# Power.net
KiCad netlist of a schematic drawn in Altium Designer
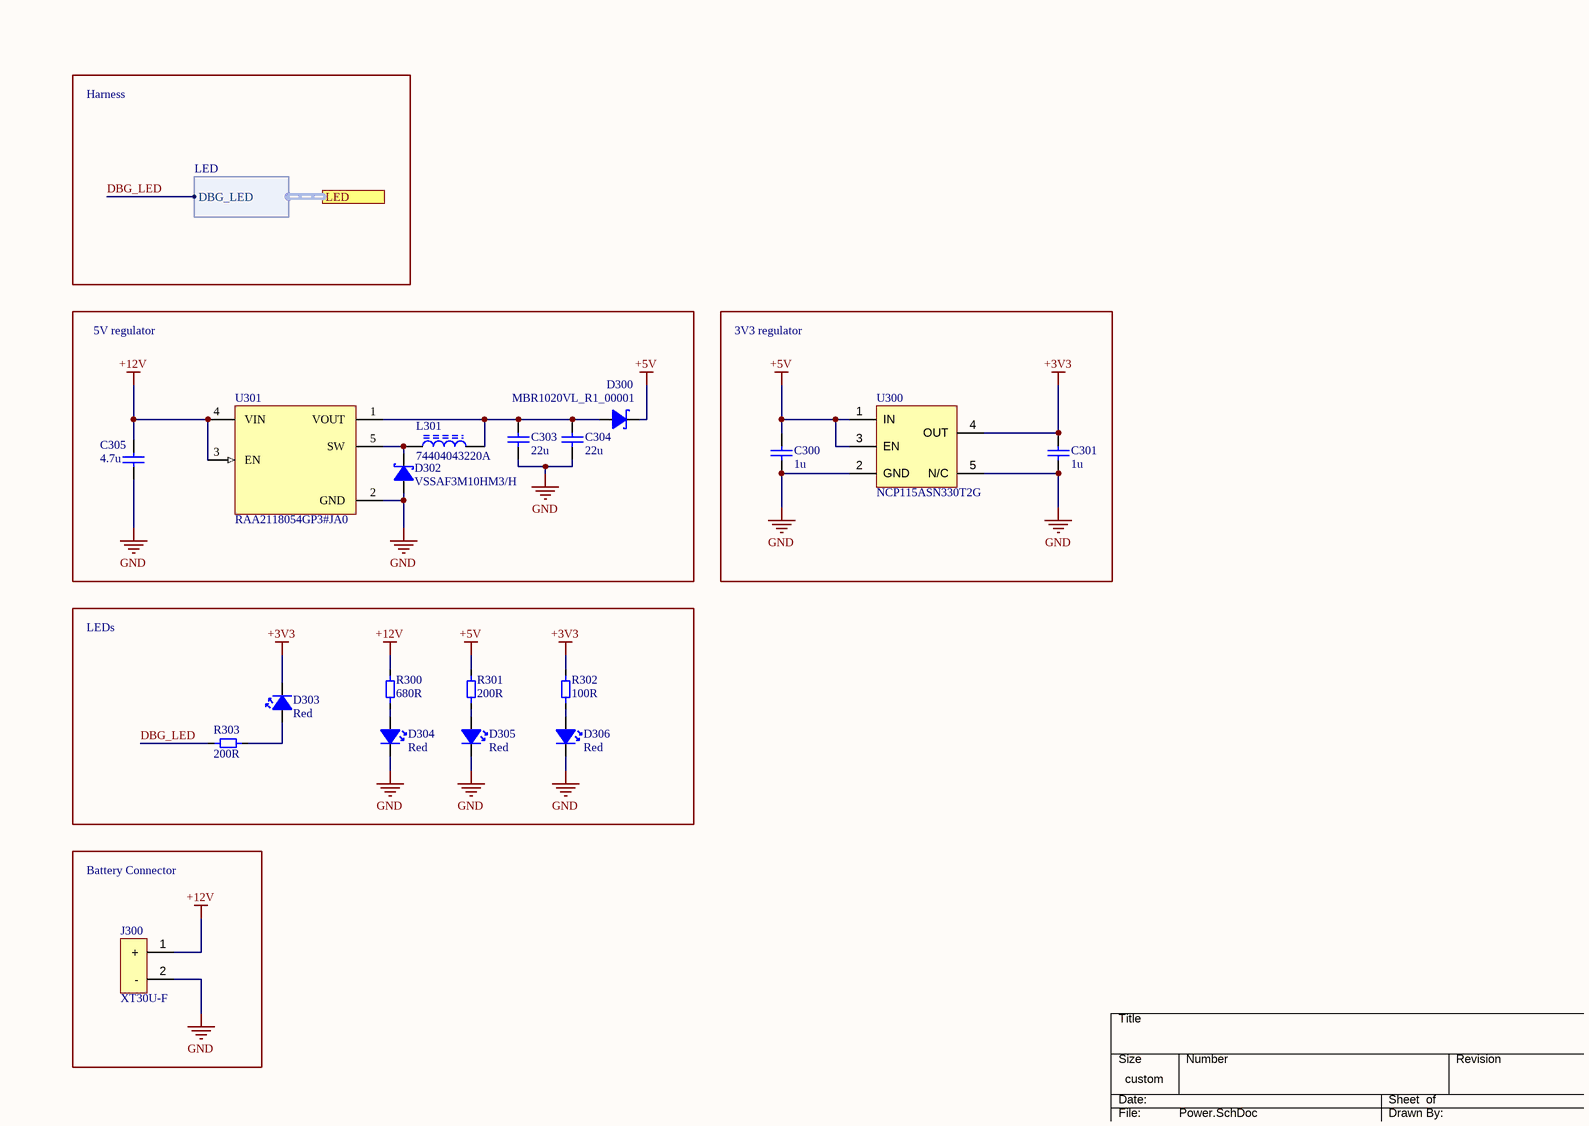
[diagram p0: Power.SchDoc]

(export (version "E")
  (design (tool "Eeschema 10.0.6"))
  (components
    (comp (ref "C300")
      (value "1u")
      (footprint "MLCC_0603_M")
      (description "MLCC, 0603, 1u, 10%, 50V, X5R")
      (fields (field (name "MANUFACTURER") "Any") (field (name "VOLTAGE") "50V"))
      (libsource (lib "Krakul Vault") (part "CAPACITOR_NONPOL_IEC"))
    )
    (comp (ref "C301")
      (value "1u")
      (footprint "MLCC_0603_M")
      (description "MLCC, 0603, 1u, 10%, 50V, X5R")
      (fields (field (name "MANUFACTURER") "Any") (field (name "VOLTAGE") "50V"))
      (libsource (lib "Krakul Vault") (part "CAPACITOR_NONPOL_IEC"))
    )
    (comp (ref "C303")
      (value "22u")
      (footprint "MLCC_0603_M")
      (description "MLCC, 0603, 22u, 10%, 16V, X5R")
      (fields (field (name "TOLERANCE") "10%") (field (name "MANUFACTURER") "Any"))
      (libsource (lib "Krakul Vault") (part "CAPACITOR_NONPOL_IEC"))
    )
    (comp (ref "C304")
      (value "22u")
      (footprint "MLCC_0603_M")
      (description "MLCC, 0603, 22u, 10%, 16V, X5R")
      (fields (field (name "TOLERANCE") "10%") (field (name "MANUFACTURER") "Any"))
      (libsource (lib "Krakul Vault") (part "CAPACITOR_NONPOL_IEC"))
    )
    (comp (ref "C305")
      (value "4.7u")
      (footprint "MLCC_1206_M")
      (description "MLCC, 1206, 4.7u, 10%, 35V, X5R")
      (fields (field (name "VOLTAGE") "35V") (field (name "TOLERANCE") "10%"))
      (libsource (lib "Krakul Vault") (part "CAPACITOR_NONPOL_IEC"))
    )
    (comp (ref "D300")
      (value "MBR1020VL_R1_00001")
      (footprint "FP-MBR1020VL_R1_00001-MFG")
      (description "Rectifier Diode, Schottky, 1 Phase, 1 Element, 1A, 20V V(RRM), Silicon")
      (fields (field (name "MANUFACTURER") "Panjit"))
      (libsource (lib "Krakul Vault") (part "Schottky generic 2 pins"))
    )
    (comp (ref "D302")
      (value "VSSAF3M10HM3/H")
      (footprint "VSSAF3M10HM3_H-Footprint-1")
      (description "Rectifier Diode, Schottky, 1 Phase, 1 Element, 2.3A, 100V V(RRM), Silicon, DO-221AC")
      (libsource (lib "Krakul Vault") (part "Schottky generic 2 pins"))
    )
    (comp (ref "D303")
      (value "Red")
      (footprint "0603 RED LED")
      (description "Generic red 0603 LED")
      (fields (field (name "PART NUMBER") "Any Red 0603 LED") (field (name "MANUFACTURER") "Any"))
      (libsource (lib "Krakul Vault") (part "LED generic"))
    )
    (comp (ref "D304")
      (value "Red")
      (footprint "0603 RED LED")
      (description "Generic red 0603 LED")
      (fields (field (name "PART NUMBER") "Any Red 0603 LED") (field (name "MANUFACTURER") "Any"))
      (libsource (lib "Krakul Vault") (part "LED generic"))
    )
    (comp (ref "D305")
      (value "Red")
      (footprint "0603 RED LED")
      (description "Generic red 0603 LED")
      (fields (field (name "PART NUMBER") "Any Red 0603 LED") (field (name "MANUFACTURER") "Any"))
      (libsource (lib "Krakul Vault") (part "LED generic"))
    )
    (comp (ref "D306")
      (value "Red")
      (footprint "0603 RED LED")
      (description "Generic red 0603 LED")
      (fields (field (name "PART NUMBER") "Any Red 0603 LED") (field (name "MANUFACTURER") "Any"))
      (libsource (lib "Krakul Vault") (part "LED generic"))
    )
    (comp (ref "J300")
      (value "XT30U-F")
      (footprint "XT30U-F")
      (description "Power Connector")
      (fields (field (name "MANUFACTURER") "AMASS"))
      (libsource (lib "Krakul Vault") (part "XT30U-F-Symbol-1"))
    )
    (comp (ref "L301")
      (value "74404043220A")
      (footprint "WE-LQS_4025")
      (description "General Purpose Inductor, 22uH, 20%, 1 Element, Nickel-zinc Ferrite-Core, SMD, 1616")
      (fields (field (name "MANUFACTURER") "Wurth Elektronik"))
      (libsource (lib "Krakul Vault") (part "INDUCTOR_SHIELDED"))
    )
    (comp (ref "R300")
      (value "680R")
      (footprint "Resistor_0603_M")
      (description "Resistor, 0603, 680R, 1%, 1/10W")
      (fields (field (name "POWER") "100mW") (field (name "TOLERANCE") "1%"))
      (libsource (lib "Krakul Vault") (part "RESISTOR_GENERIC_IEC"))
    )
    (comp (ref "R301")
      (value "200R")
      (footprint "Resistor_0603_M")
      (description "Resistor, 0603, 200R, 1%, 1/10W")
      (fields (field (name "TOLERANCE") "1%") (field (name "POWER") "100mW"))
      (libsource (lib "Krakul Vault") (part "RESISTOR_GENERIC_IEC"))
    )
    (comp (ref "R302")
      (value "100R")
      (footprint "Resistor_0603_M")
      (description "Resistor, 0603, 100R, ≤5%, ≥1/16W")
      (fields (field (name "MANUFACTURER") "Any"))
      (libsource (lib "Krakul Vault") (part "RESISTOR_GENERIC_IEC"))
    )
    (comp (ref "R303")
      (value "200R")
      (footprint "Resistor_0603_M")
      (description "Resistor, 0603, 200R, 1%, 1/10W")
      (fields (field (name "TOLERANCE") "1%") (field (name "POWER") "100mW"))
      (libsource (lib "Krakul Vault") (part "RESISTOR_GENERIC_IEC"))
    )
    (comp (ref "U300")
      (value "NCP115ASN330T2G")
      (footprint "TSOP-5")
      (fields (field (name "MANUFACTURER") "onsemi"))
      (libsource (lib "Krakul Vault") (part "NCP115ASN330T2G"))
    )
    (comp (ref "U301")
      (value "RAA2118054GP3#JA0")
      (footprint "P5_064B_MFG")
      (description "Switching Regulator, Current-mode, 0.3A, 230kHz Switching Freq-Max, PDSO5")
      (fields (field (name "MANUFACTURER") "Renesas / Intersil"))
      (libsource (lib "Krakul Vault") (part "04ef17e7ed04f306c00cc4b237f44d7"))
    )
  )
  (nets
    (net (code "2") (name "+3V3") (class "Default")
      (node (ref "C301") (pin "2") (pinfunction "2_2") (pintype "passive"))
      (node (ref "D303") (pin "1") (pinfunction "C_1") (pintype "passive"))
      (node (ref "R302") (pin "2") (pinfunction "2_2") (pintype "passive"))
      (node (ref "U300") (pin "4") (pinfunction "OUT_4") (pintype "passive"))
    )
    (net (code "3") (name "+5V") (class "Default")
      (node (ref "C300") (pin "2") (pinfunction "2_2") (pintype "passive"))
      (node (ref "D300") (pin "1") (pinfunction "C_1") (pintype "passive"))
      (node (ref "R301") (pin "1") (pinfunction "1_1") (pintype "passive"))
      (node (ref "U300") (pin "1") (pinfunction "IN_1") (pintype "passive"))
      (node (ref "U300") (pin "3") (pinfunction "EN_3") (pintype "passive"))
    )
    (net (code "4") (name "+12V") (class "Default")
      (node (ref "C305") (pin "2") (pinfunction "2_2") (pintype "passive"))
      (node (ref "J300") (pin "1") (pinfunction "+_1") (pintype "passive"))
      (node (ref "R300") (pin "2") (pinfunction "2_2") (pintype "passive"))
      (node (ref "U301") (pin "3") (pinfunction "EN_3") (pintype "input"))
      (node (ref "U301") (pin "4") (pinfunction "VIN_4") (pintype "power_in"))
    )
    (net (code "5") (name "/DBG_LED") (class "Default")
      (node (ref "R303") (pin "1") (pinfunction "1_1") (pintype "passive"))
    )
    (net (code "7") (name "GND") (class "Default")
      (node (ref "C300") (pin "1") (pinfunction "1_1") (pintype "passive"))
      (node (ref "C301") (pin "1") (pinfunction "1_1") (pintype "passive"))
      (node (ref "C303") (pin "1") (pinfunction "1_1") (pintype "passive"))
      (node (ref "C304") (pin "1") (pinfunction "1_1") (pintype "passive"))
      (node (ref "C305") (pin "1") (pinfunction "1_1") (pintype "passive"))
      (node (ref "D302") (pin "2") (pinfunction "A_2") (pintype "passive"))
      (node (ref "D304") (pin "1") (pinfunction "C_1") (pintype "passive"))
      (node (ref "D305") (pin "1") (pinfunction "C_1") (pintype "passive"))
      (node (ref "D306") (pin "1") (pinfunction "C_1") (pintype "passive"))
      (node (ref "J300") (pin "2") (pinfunction "-_2") (pintype "passive"))
      (node (ref "U300") (pin "2") (pinfunction "GND_2") (pintype "passive"))
      (node (ref "U300") (pin "5") (pinfunction "N/C_5") (pintype "passive"))
      (node (ref "U301") (pin "2") (pinfunction "GND_2") (pintype "power_in"))
    )
    (net (code "8") (name "Net-(D300-A)") (class "Default")
      (node (ref "C303") (pin "2") (pinfunction "2_2") (pintype "passive"))
      (node (ref "C304") (pin "2") (pinfunction "2_2") (pintype "passive"))
      (node (ref "D300") (pin "2") (pinfunction "A_2") (pintype "passive"))
      (node (ref "L301") (pin "2") (pinfunction "2_2") (pintype "passive"))
      (node (ref "U301") (pin "1") (pinfunction "VOUT_1") (pintype "power_in"))
    )
    (net (code "9") (name "Net-(D302-C)") (class "Default")
      (node (ref "D302") (pin "1") (pinfunction "C_1") (pintype "passive"))
      (node (ref "L301") (pin "1") (pinfunction "1_1") (pintype "passive"))
      (node (ref "U301") (pin "5") (pinfunction "SW_5") (pintype "passive"))
    )
    (net (code "10") (name "Net-(D303-A)") (class "Default")
      (node (ref "D303") (pin "2") (pinfunction "A_2") (pintype "passive"))
      (node (ref "R303") (pin "2") (pinfunction "2_2") (pintype "passive"))
    )
    (net (code "11") (name "Net-(D304-A)") (class "Default")
      (node (ref "D304") (pin "2") (pinfunction "A_2") (pintype "passive"))
      (node (ref "R300") (pin "1") (pinfunction "1_1") (pintype "passive"))
    )
    (net (code "12") (name "Net-(D305-A)") (class "Default")
      (node (ref "D305") (pin "2") (pinfunction "A_2") (pintype "passive"))
      (node (ref "R301") (pin "2") (pinfunction "2_2") (pintype "passive"))
    )
    (net (code "13") (name "Net-(D306-A)") (class "Default")
      (node (ref "D306") (pin "2") (pinfunction "A_2") (pintype "passive"))
      (node (ref "R302") (pin "1") (pinfunction "1_1") (pintype "passive"))
    )
  )
)
